# design.net
KiCad netlist of a schematic drawn in Altium Designer
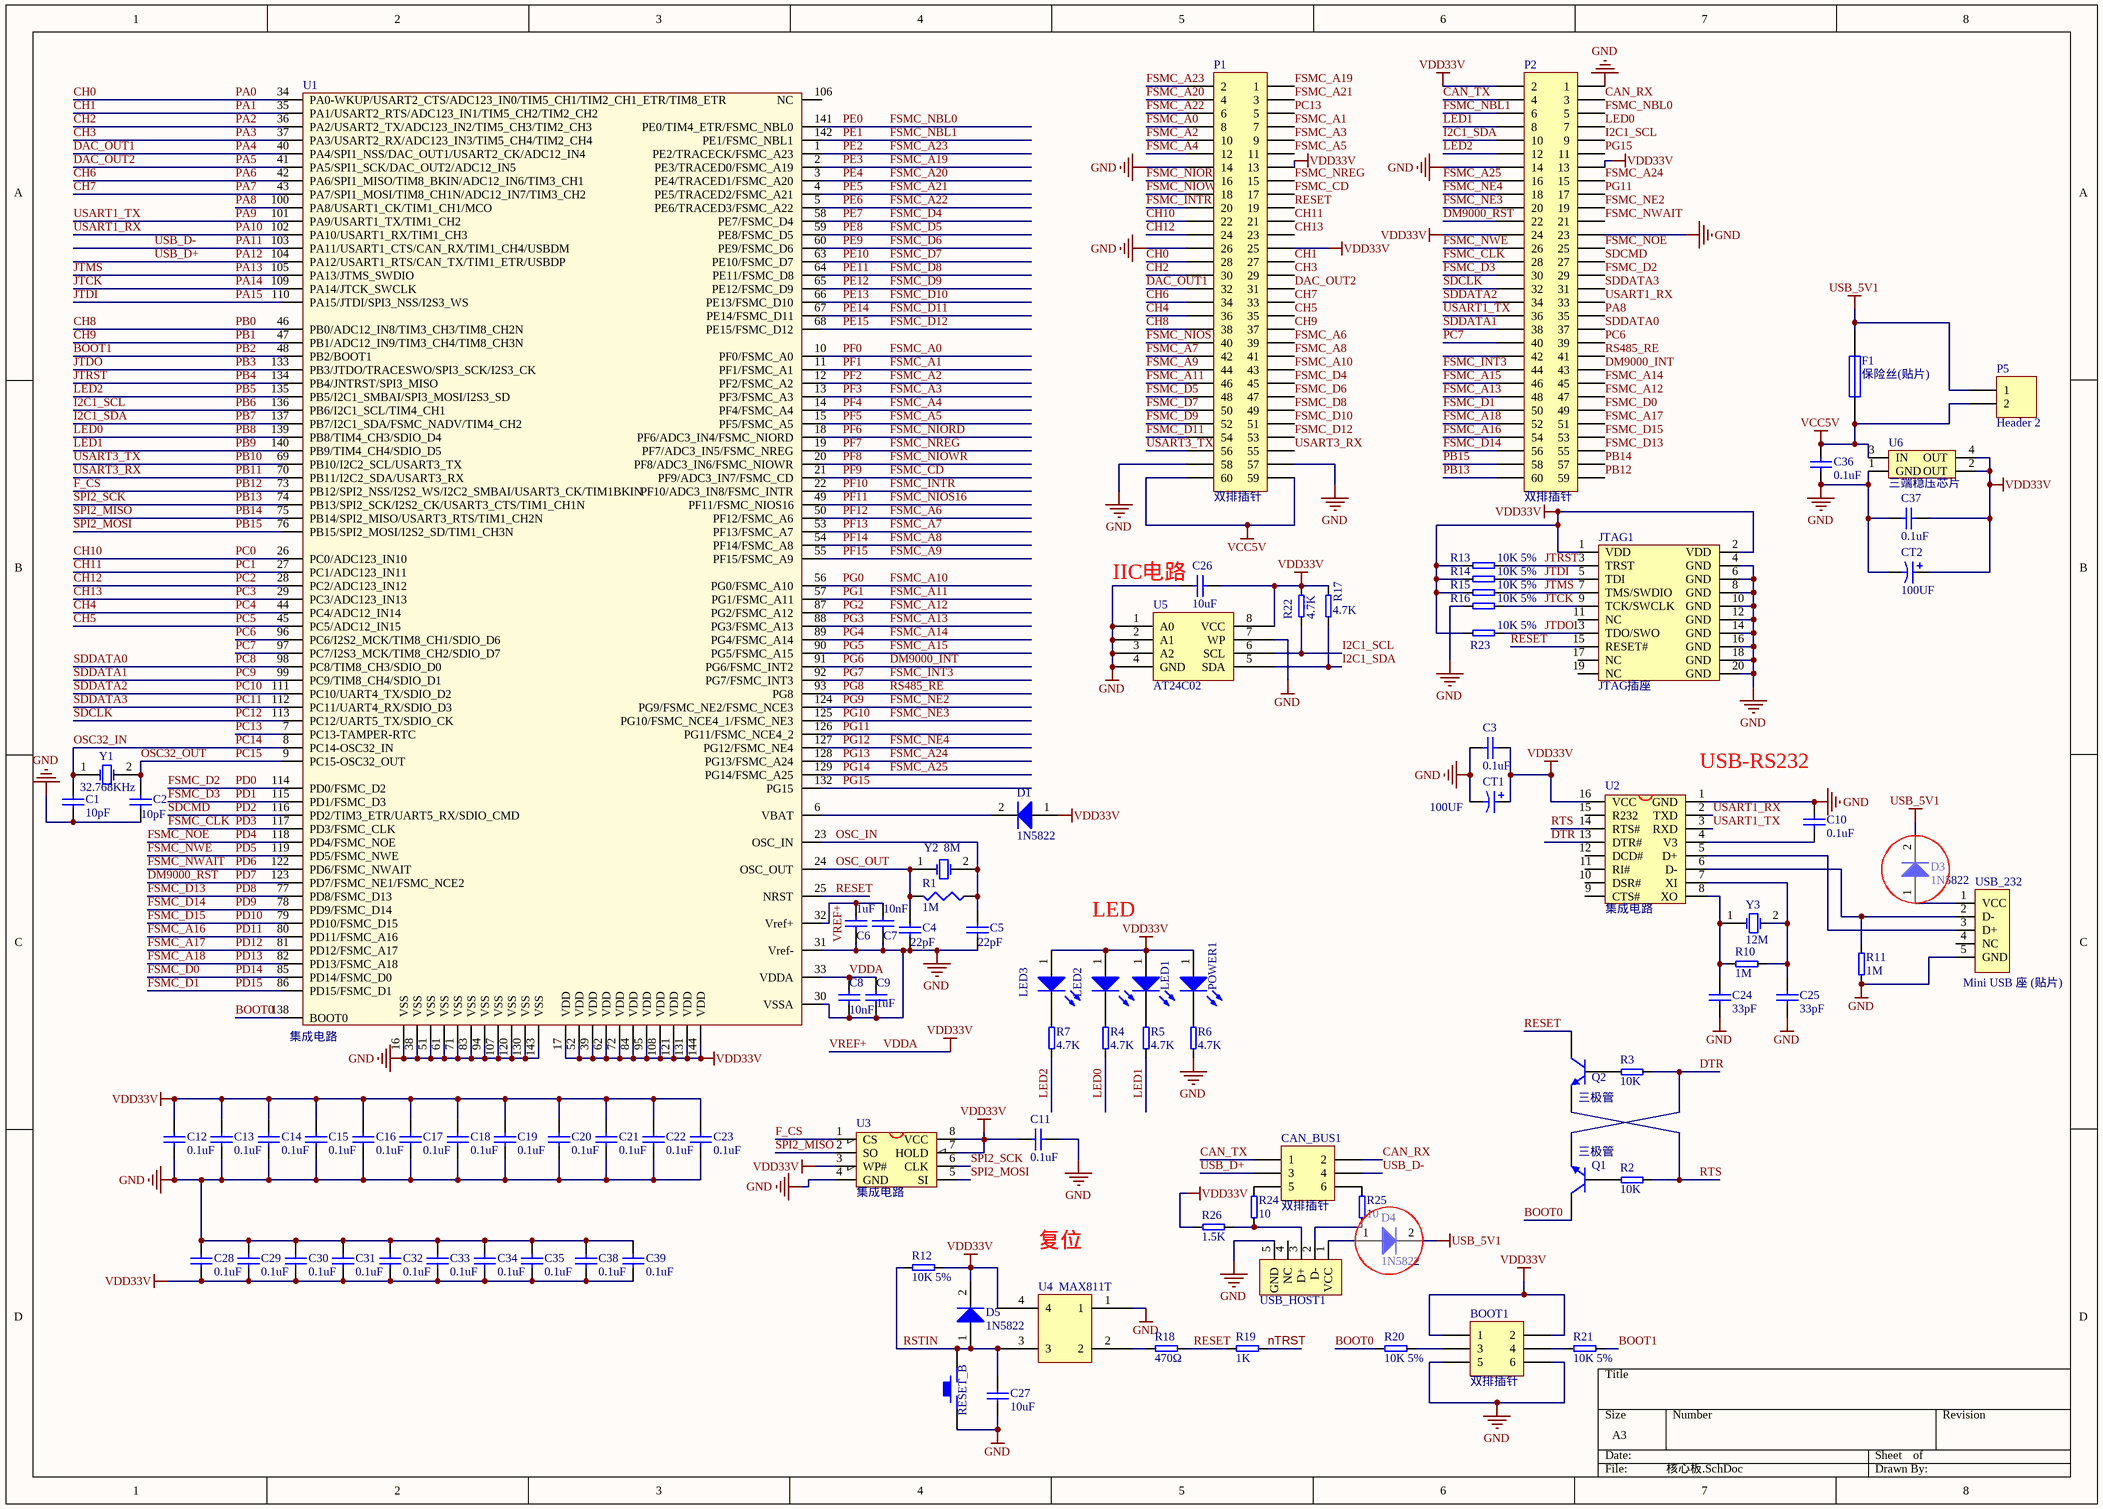
[diagram p0: 核心板.SchDoc]

(export (version "E")
  (design (tool "Eeschema 10.0.6"))
  (components
    (comp (ref "BOOT1")
      (value "双排插针")
      (footprint "HDR2X3")
      (description "2x3 脚间距2.54")
      (fields (field (name "PUBLISHER") "Altium Limited"))
      (libsource (lib "Miscellaneous Connectors") (part "Header 3X2"))
    )
    (comp (ref "C1")
      (value "10pF")
      (footprint "0603")
      (description "CAP 10PF 50V CERAMIC 0603 SMD")
      (fields (field (name "Comment") "电容(贴片)") (field (name "PUBLISHER") "Altium Limited"))
      (libsource (lib "Miscellaneous Devices") (part "Cap"))
    )
    (comp (ref "C2")
      (value "10pF")
      (footprint "0603")
      (description "CAP 10PF 50V CERAMIC 0603 SMD")
      (fields (field (name "Comment") "电容(贴片)") (field (name "PUBLISHER") "Altium Limited"))
      (libsource (lib "Miscellaneous Devices") (part "Cap"))
    )
    (comp (ref "C3")
      (value "0.1uF")
      (footprint "0603")
      (description "0603X7R104J160NT(0.1uF)")
      (fields (field (name "Comment") "电容(贴片)"))
      (libsource (lib "altium-import") (part "root_2_mirrored_CAP_0.1uF X7R 0603_"))
    )
    (comp (ref "C4")
      (value "22pF")
      (footprint "0603")
      (description "CAP 22PF 50V CERAMIC 0603 SMD")
      (fields (field (name "Comment") "电容(贴片)") (field (name "PUBLISHER") "Altium Limited"))
      (libsource (lib "Miscellaneous Devices") (part "Cap"))
    )
    (comp (ref "C5")
      (value "22pF")
      (footprint "0603")
      (description "CAP 22PF 50V CERAMIC 0603 SMD")
      (fields (field (name "Comment") "电容(贴片)") (field (name "PUBLISHER") "Altium Limited"))
      (libsource (lib "Miscellaneous Devices") (part "Cap"))
    )
    (comp (ref "C6")
      (value "1uF")
      (footprint "0603")
      (description "CAP 1uf 16V CERAMIC X5R 0603")
      (fields (field (name "Comment") "电容(贴片)") (field (name "PUBLISHER") "Altium Limited"))
      (libsource (lib "Miscellaneous Devices") (part "Cap"))
    )
    (comp (ref "C7")
      (value "10nF")
      (footprint "0603")
      (description "CAP 10nf 16V CERAMIC X5R 0603")
      (fields (field (name "Comment") "电容(贴片)") (field (name "PUBLISHER") "Altium Limited"))
      (libsource (lib "Miscellaneous Devices") (part "Cap"))
    )
    (comp (ref "C8")
      (value "10nF")
      (footprint "0603")
      (description "CAP 10nf 16V CERAMIC X5R 0603")
      (fields (field (name "Comment") "电容(贴片)") (field (name "PUBLISHER") "Altium Limited"))
      (libsource (lib "Miscellaneous Devices") (part "Cap"))
    )
    (comp (ref "C9")
      (value "1uF")
      (footprint "0603")
      (description "CAP 1uf 16V CERAMIC X5R 0603")
      (fields (field (name "Comment") "电容(贴片)") (field (name "PUBLISHER") "Altium Limited"))
      (libsource (lib "Miscellaneous Devices") (part "Cap"))
    )
    (comp (ref "C10")
      (value "0.1uF")
      (footprint "0603")
      (description "0603X7R104J160NT(0.1uF)")
      (fields (field (name "Comment") "电容(贴片)"))
      (libsource (lib "altium-import") (part "root_3_mirrored_CAP_0.1uF X7R 0603_"))
    )
    (comp (ref "C11")
      (value "0.1uF")
      (footprint "0603")
      (description "0603X7R104J160NT(0.1uF)")
      (fields (field (name "Comment") "电容(贴片)"))
      (libsource (lib "altium-import") (part "root_2_mirrored_CAP_0.1uF X7R 0603_"))
    )
    (comp (ref "C12")
      (value "0.1uF")
      (footprint "0603")
      (description "0603X7R104J160NT(0.1uF)")
      (fields (field (name "Comment") "电容(贴片)"))
      (libsource (lib "altium-import") (part "root_3_mirrored_CAP_0.1uF X7R 0603_"))
    )
    (comp (ref "C13")
      (value "0.1uF")
      (footprint "0603")
      (description "0603X7R104J160NT(0.1uF)")
      (fields (field (name "Comment") "电容(贴片)"))
      (libsource (lib "altium-import") (part "root_3_mirrored_CAP_0.1uF X7R 0603_"))
    )
    (comp (ref "C14")
      (value "0.1uF")
      (footprint "0603")
      (description "0603X7R104J160NT(0.1uF)")
      (fields (field (name "Comment") "电容(贴片)"))
      (libsource (lib "altium-import") (part "root_3_mirrored_CAP_0.1uF X7R 0603_"))
    )
    (comp (ref "C15")
      (value "0.1uF")
      (footprint "0603")
      (description "0603X7R104J160NT(0.1uF)")
      (fields (field (name "Comment") "电容(贴片)"))
      (libsource (lib "altium-import") (part "root_3_mirrored_CAP_0.1uF X7R 0603_"))
    )
    (comp (ref "C16")
      (value "0.1uF")
      (footprint "0603")
      (description "0603X7R104J160NT(0.1uF)")
      (fields (field (name "Comment") "电容(贴片)"))
      (libsource (lib "altium-import") (part "root_3_mirrored_CAP_0.1uF X7R 0603_"))
    )
    (comp (ref "C17")
      (value "0.1uF")
      (footprint "0603")
      (description "0603X7R104J160NT(0.1uF)")
      (fields (field (name "Comment") "电容(贴片)"))
      (libsource (lib "altium-import") (part "root_3_mirrored_CAP_0.1uF X7R 0603_"))
    )
    (comp (ref "C18")
      (value "0.1uF")
      (footprint "0603")
      (description "0603X7R104J160NT(0.1uF)")
      (fields (field (name "Comment") "电容(贴片)"))
      (libsource (lib "altium-import") (part "root_3_mirrored_CAP_0.1uF X7R 0603_"))
    )
    (comp (ref "C19")
      (value "0.1uF")
      (footprint "0603")
      (description "0603X7R104J160NT(0.1uF)")
      (fields (field (name "Comment") "电容(贴片)"))
      (libsource (lib "altium-import") (part "root_3_mirrored_CAP_0.1uF X7R 0603_"))
    )
    (comp (ref "C20")
      (value "0.1uF")
      (footprint "0603")
      (description "0603X7R104J160NT(0.1uF)")
      (fields (field (name "Comment") "电容(贴片)"))
      (libsource (lib "altium-import") (part "root_3_mirrored_CAP_0.1uF X7R 0603_"))
    )
    (comp (ref "C21")
      (value "0.1uF")
      (footprint "0603")
      (description "0603X7R104J160NT(0.1uF)")
      (fields (field (name "Comment") "电容(贴片)"))
      (libsource (lib "altium-import") (part "root_3_mirrored_CAP_0.1uF X7R 0603_"))
    )
    (comp (ref "C22")
      (value "0.1uF")
      (footprint "0603")
      (description "0603X7R104J160NT(0.1uF)")
      (fields (field (name "Comment") "电容(贴片)"))
      (libsource (lib "altium-import") (part "root_3_mirrored_CAP_0.1uF X7R 0603_"))
    )
    (comp (ref "C23")
      (value "0.1uF")
      (footprint "0603")
      (description "0603X7R104J160NT(0.1uF)")
      (fields (field (name "Comment") "电容(贴片)"))
      (libsource (lib "altium-import") (part "root_3_mirrored_CAP_0.1uF X7R 0603_"))
    )
    (comp (ref "C24")
      (value "33pF")
      (footprint "0603")
      (description "0603COG330J500NT(33pF)")
      (fields (field (name "Comment") "电容(贴片)"))
      (libsource (lib "altium-import") (part "root_1_mirrored_CAP_33pF COG 0603_"))
    )
    (comp (ref "C25")
      (value "33pF")
      (footprint "0603")
      (description "0603COG330J500NT(33pF)")
      (fields (field (name "Comment") "电容(贴片)"))
      (libsource (lib "altium-import") (part "root_1_mirrored_CAP_33pF COG 0603_"))
    )
    (comp (ref "C26")
      (value "10uF")
      (footprint "0603")
      (description "0603Z5U106J100NT(10uF/10V)")
      (fields (field (name "Comment") "电容(贴片)"))
      (libsource (lib "altium-import") (part "root_0_CAP_10uF/10V Z5U 0603_"))
    )
    (comp (ref "C27")
      (value "10uF")
      (footprint "0603")
      (description "0603Z5U106J100NT(10uF/10V)")
      (fields (field (name "Comment") "电容(贴片)"))
      (libsource (lib "altium-import") (part "root_3_CAP_10uF/10V Z5U 0603_"))
    )
    (comp (ref "C28")
      (value "0.1uF")
      (footprint "0603")
      (description "0603X7R104J160NT(0.1uF)")
      (fields (field (name "Comment") "电容(贴片)"))
      (libsource (lib "altium-import") (part "root_3_mirrored_CAP_0.1uF X7R 0603_"))
    )
    (comp (ref "C29")
      (value "0.1uF")
      (footprint "0603")
      (description "0603X7R104J160NT(0.1uF)")
      (fields (field (name "Comment") "电容(贴片)"))
      (libsource (lib "altium-import") (part "root_3_mirrored_CAP_0.1uF X7R 0603_"))
    )
    (comp (ref "C30")
      (value "0.1uF")
      (footprint "0603")
      (description "0603X7R104J160NT(0.1uF)")
      (fields (field (name "Comment") "电容(贴片)"))
      (libsource (lib "altium-import") (part "root_3_mirrored_CAP_0.1uF X7R 0603_"))
    )
    (comp (ref "C31")
      (value "0.1uF")
      (footprint "0603")
      (description "0603X7R104J160NT(0.1uF)")
      (fields (field (name "Comment") "电容(贴片)"))
      (libsource (lib "altium-import") (part "root_3_mirrored_CAP_0.1uF X7R 0603_"))
    )
    (comp (ref "C32")
      (value "0.1uF")
      (footprint "0603")
      (description "0603X7R104J160NT(0.1uF)")
      (fields (field (name "Comment") "电容(贴片)"))
      (libsource (lib "altium-import") (part "root_3_mirrored_CAP_0.1uF X7R 0603_"))
    )
    (comp (ref "C33")
      (value "0.1uF")
      (footprint "0603")
      (description "0603X7R104J160NT(0.1uF)")
      (fields (field (name "Comment") "电容(贴片)"))
      (libsource (lib "altium-import") (part "root_3_mirrored_CAP_0.1uF X7R 0603_"))
    )
    (comp (ref "C34")
      (value "0.1uF")
      (footprint "0603")
      (description "0603X7R104J160NT(0.1uF)")
      (fields (field (name "Comment") "电容(贴片)"))
      (libsource (lib "altium-import") (part "root_3_mirrored_CAP_0.1uF X7R 0603_"))
    )
    (comp (ref "C35")
      (value "0.1uF")
      (footprint "0603")
      (description "0603X7R104J160NT(0.1uF)")
      (fields (field (name "Comment") "电容(贴片)"))
      (libsource (lib "altium-import") (part "root_3_mirrored_CAP_0.1uF X7R 0603_"))
    )
    (comp (ref "C36")
      (value "0.1uF")
      (footprint "0603")
      (description "0603X7R104J160NT(0.1uF)")
      (fields (field (name "Comment") "电容(贴片)"))
      (libsource (lib "altium-import") (part "root_3_mirrored_CAP_0.1uF X7R 0603_"))
    )
    (comp (ref "C37")
      (value "0.1uF")
      (footprint "0603")
      (description "0603X7R104J160NT(0.1uF)")
      (fields (field (name "Comment") "电容(贴片)"))
      (libsource (lib "altium-import") (part "root_0_mirrored_CAP_0.1uF X7R 0603_"))
    )
    (comp (ref "C38")
      (value "0.1uF")
      (footprint "0603")
      (description "0603X7R104J160NT(0.1uF)")
      (fields (field (name "Comment") "电容(贴片)"))
      (libsource (lib "altium-import") (part "root_3_mirrored_CAP_0.1uF X7R 0603_"))
    )
    (comp (ref "C39")
      (value "0.1uF")
      (footprint "0603")
      (description "0603X7R104J160NT(0.1uF)")
      (fields (field (name "Comment") "电容(贴片)"))
      (libsource (lib "altium-import") (part "root_3_mirrored_CAP_0.1uF X7R 0603_"))
    )
    (comp (ref "CAN_BUS1")
      (value "双排插针")
      (footprint "HDR2X3")
      (description "2x3 Pin 脚间距2.54mm")
      (fields (field (name "PUBLISHER") "Altium Limited"))
      (libsource (lib "Miscellaneous Connectors") (part "Header 3X2"))
    )
    (comp (ref "CT1")
      (value "100UF")
      (footprint "6032")
      (description "CAP TANTALUM 100UF 16V 20% SMD")
      (fields (field (name "Comment") "钽电容(贴片)"))
      (libsource (lib "altium-import") (part "root_1_mirrored_CAP TAN 100uF/10V/6032_"))
    )
    (comp (ref "CT2")
      (value "100UF")
      (footprint "6032")
      (description "CAP TANTALUM 100UF 16V 20% SMD")
      (fields (field (name "Comment") "钽电容(贴片)"))
      (libsource (lib "altium-import") (part "root_1_mirrored_CAP TAN 100uF/10V/6032_"))
    )
    (comp (ref "D1")
      (value "1N5822")
      (footprint "D1206")
      (description "1N5822/1206")
      (fields (field (name "Comment") "二极管(贴片)"))
      (libsource (lib "altium-import") (part "root_0_mirrored_DIODE 1N4148/1206_"))
    )
    (comp (ref "D3")
      (value "1N5822")
      (footprint "D1206")
      (description "1N5822/1206")
      (fields (field (name "Comment") "二极管(贴片)"))
      (libsource (lib "altium-import") (part "root_3_mirrored_DIODE 1N4148/1206_"))
    )
    (comp (ref "D4")
      (value "1N5822")
      (footprint "D1206")
      (description "1N5822/1206")
      (fields (field (name "Comment") "二极管(贴片)"))
      (libsource (lib "altium-import") (part "root_2_mirrored_DIODE 1N4148/1206_"))
    )
    (comp (ref "D5")
      (value "1N5822")
      (footprint "D1206")
      (description "1N5822/1206")
      (fields (field (name "Comment") "二极管(贴片)"))
      (libsource (lib "altium-import") (part "root_1_DIODE 1N4148/1206_"))
    )
    (comp (ref "F1")
      (value "保险丝(贴片)")
      (footprint "0805")
      (description "0.5A 0805")
      (fields (field (name "PUBLISHER") "Altium Limited"))
      (libsource (lib "Miscellaneous Devices") (part "Fuse 1"))
    )
    (comp (ref "JTAG1")
      (value "JTAG插座")
      (footprint "JTAG_20")
      (description "20P 黑色 带缺口")
      (libsource (lib "WarShip V3 STM32103封装库") (part "JTAG"))
    )
    (comp (ref "LED1")
      (value "二极管(贴片发光绿色)")
      (footprint "LED-0805")
      (description "17-215SYGC-S530-E2-TR8")
      (libsource (lib "SCH_XIJUN") (part "LED_GREEN 0805"))
    )
    (comp (ref "LED2")
      (value "二极管(贴片发光绿色)")
      (footprint "LED-0805")
      (description "17-215SYGC-S530-E2-TR8")
      (libsource (lib "SCH_XIJUN") (part "LED_GREEN 0805"))
    )
    (comp (ref "LED3")
      (value "二极管(贴片发光绿色)")
      (footprint "LED-0805")
      (description "17-215SYGC-S530-E2-TR8")
      (libsource (lib "SCH_XIJUN") (part "LED_GREEN 0805"))
    )
    (comp (ref "P1")
      (value "双排插针")
      (footprint "HDR2X30")
      (description "双排 30*2P 脚间距 2.54mm")
      (fields (field (name "PUBLISHER") "Altium Limited"))
      (libsource (lib "Miscellaneous Connectors") (part "Header 30X2"))
    )
    (comp (ref "P2")
      (value "双排插针")
      (footprint "HDR2X30")
      (description "双排 30*2P 脚间距 2.54mm")
      (fields (field (name "PUBLISHER") "Altium Limited"))
      (libsource (lib "Miscellaneous Connectors") (part "Header 30X2"))
    )
    (comp (ref "P5")
      (value "Header 2")
      (footprint "HDR1X2")
      (description "Header, 2-Pin")
      (fields (field (name "PUBLISHER") "Altium Limited"))
      (libsource (lib "Miscellaneous Connectors") (part "Header 2"))
    )
    (comp (ref "POWER1")
      (value "二极管(贴片发光红色)")
      (footprint "LED-0805")
      (description "17-215-SURC-S530-A3-TR8")
      (libsource (lib "SCH_XIJUN") (part "LED_GREEN 0805"))
    )
    (comp (ref "Q1")
      (value "三极管")
      (footprint "sot-23")
      (description "S8050 NPN General Purpose Amplifier")
      (fields (field (name "PUBLISHER") "Altium Limited"))
      (libsource (lib "Miscellaneous Devices") (part "2N3904"))
    )
    (comp (ref "Q2")
      (value "三极管")
      (footprint "sot-23")
      (description "S8050 NPN General Purpose Amplifier")
      (fields (field (name "PUBLISHER") "Altium Limited"))
      (libsource (lib "Miscellaneous Devices") (part "2N3904"))
    )
    (comp (ref "R1")
      (value "1M")
      (footprint "0603")
      (description "RS-03K-105±5%(1MΩ)")
      (fields (field (name "Comment") "电阻(贴片)") (field (name "PUBLISHER") "Altium Limited"))
      (libsource (lib "Miscellaneous Devices") (part "Res3"))
    )
    (comp (ref "R2")
      (value "10K")
      (footprint "0603")
      (description "RS-03K-105±5%(1MΩ)")
      (fields (field (name "Comment") "电阻(贴片)"))
      (libsource (lib "altium-import") (part "root_2_mirrored_RES_1MΩ 5% 0603_"))
    )
    (comp (ref "R3")
      (value "10K")
      (footprint "0603")
      (description "RS-03K-102±5%(1K)")
      (fields (field (name "Comment") "电阻(贴片)"))
      (libsource (lib "altium-import") (part "root_0_mirrored_RES_1MΩ 5% 0603_"))
    )
    (comp (ref "R4")
      (value "4.7K")
      (footprint "0603")
      (description "RS-03K-472±5%(4.7K)")
      (fields (field (name "Comment") "电阻(贴片)"))
      (libsource (lib "SCH_XIJUN") (part "RES_4.7K  5% 0603"))
    )
    (comp (ref "R5")
      (value "4.7K")
      (footprint "0603")
      (description "RS-03K-472±5%(4.7K)")
      (fields (field (name "Comment") "电阻(贴片)"))
      (libsource (lib "SCH_XIJUN") (part "RES_4.7K  5% 0603"))
    )
    (comp (ref "R6")
      (value "4.7K")
      (footprint "0603")
      (description "RS-03K-472±5%(4.7K)")
      (fields (field (name "Comment") "电阻(贴片)"))
      (libsource (lib "SCH_XIJUN") (part "RES_4.7K  5% 0603"))
    )
    (comp (ref "R7")
      (value "4.7K")
      (footprint "0603")
      (description "RS-03K-472±5%(4.7K)")
      (fields (field (name "Comment") "电阻(贴片)"))
      (libsource (lib "SCH_XIJUN") (part "RES_4.7K  5% 0603"))
    )
    (comp (ref "R10")
      (value "1M")
      (footprint "0603")
      (description "RS-03K-105±5%(1MΩ)")
      (fields (field (name "Comment") "电阻(贴片)"))
      (libsource (lib "altium-import") (part "root_0_mirrored_RES_1MΩ 5% 0603_"))
    )
    (comp (ref "R11")
      (value "1M")
      (footprint "0603")
      (description "RS-03K-105±5%(1MΩ)")
      (fields (field (name "Comment") "电阻(贴片)"))
      (libsource (lib "altium-import") (part "root_3_mirrored_RES_1M 5% 0603_"))
    )
    (comp (ref "R12")
      (value "10K 5%")
      (footprint "0603")
      (description "RS-03K-103±5%(10KΩ)")
      (fields (field (name "Comment") "电阻(贴片)"))
      (libsource (lib "altium-import") (part "root_2_RES_10K 5% 0603_"))
    )
    (comp (ref "R13")
      (value "10K 5%")
      (footprint "0603")
      (description "RS-03K-103±5%(10KΩ)")
      (fields (field (name "Comment") "电阻(贴片)"))
      (libsource (lib "altium-import") (part "root_0_RES_10K 5% 0603_"))
    )
    (comp (ref "R14")
      (value "10K 5%")
      (footprint "0603")
      (description "RS-03K-103±5%(10KΩ)")
      (fields (field (name "Comment") "电阻(贴片)"))
      (libsource (lib "altium-import") (part "root_0_RES_10K 5% 0603_"))
    )
    (comp (ref "R15")
      (value "10K 5%")
      (footprint "0603")
      (description "RS-03K-103±5%(10KΩ)")
      (fields (field (name "Comment") "电阻(贴片)"))
      (libsource (lib "altium-import") (part "root_0_RES_10K 5% 0603_"))
    )
    (comp (ref "R16")
      (value "10K 5%")
      (footprint "0603")
      (description "RS-03K-103±5%(10KΩ)")
      (fields (field (name "Comment") "电阻(贴片)"))
      (libsource (lib "altium-import") (part "root_0_RES_10K 5% 0603_"))
    )
    (comp (ref "R17")
      (value "4.7K")
      (footprint "0603")
      (description "RS-03K-152±5%(1.5KΩ)")
      (fields (field (name "Comment") "电阻(贴片)"))
      (libsource (lib "altium-import") (part "root_1_RES_1.5K  5% 0603_"))
    )
    (comp (ref "R18")
      (value "470Ω")
      (footprint "0603")
      (description "RS-03K-471±5%(470Ω)")
      (fields (field (name "Comment") "电阻(贴片)"))
      (libsource (lib "altium-import") (part "root_2_RES_470 5% 0603_"))
    )
    (comp (ref "R19")
      (value "1K")
      (footprint "0603")
      (description "RS-03K-102±5%(1K)")
      (fields (field (name "Comment") "电阻(贴片)"))
      (libsource (lib "altium-import") (part "root_0_RES_1K  5% 0603_"))
    )
    (comp (ref "R20")
      (value "10K 5%")
      (footprint "0603")
      (description "RS-03K-103±5%(10KΩ)")
      (fields (field (name "Comment") "电阻(贴片)"))
      (libsource (lib "altium-import") (part "root_2_RES_10K 5% 0603_"))
    )
    (comp (ref "R21")
      (value "10K 5%")
      (footprint "0603")
      (description "RS-03K-103±5%(10KΩ)")
      (fields (field (name "Comment") "电阻(贴片)"))
      (libsource (lib "altium-import") (part "root_2_RES_10K 5% 0603_"))
    )
    (comp (ref "R22")
      (value "4.7K")
      (footprint "0603")
      (description "RS-03K-152±5%(1.5KΩ)")
      (fields (field (name "Comment") "电阻(贴片)"))
      (libsource (lib "altium-import") (part "root_1_RES_1.5K  5% 0603_"))
    )
    (comp (ref "R23")
      (value "10K 5%")
      (footprint "0603")
      (description "RS-03K-103±5%(10KΩ)")
      (fields (field (name "Comment") "电阻(贴片)"))
      (libsource (lib "altium-import") (part "root_0_RES_10K 5% 0603_"))
    )
    (comp (ref "R24")
      (value "10")
      (footprint "0603")
      (description "RS-03K-100±5%(10)")
      (fields (field (name "Comment") "电阻(贴片)"))
      (libsource (lib "SCH_XIJUN") (part "RES_1K  5% 0603"))
    )
    (comp (ref "R25")
      (value "10")
      (footprint "0603")
      (description "RS-03K-100±5%(10)")
      (fields (field (name "Comment") "电阻(贴片)"))
      (libsource (lib "SCH_XIJUN") (part "RES_1K  5% 0603"))
    )
    (comp (ref "R26")
      (value "1.5K")
      (footprint "0603")
      (description "RS-03K-152±5%(1.5K)")
      (fields (field (name "Comment") "电阻(贴片)"))
      (libsource (lib "SCH_XIJUN") (part "RES_1.5K  5% 0603"))
    )
    (comp (ref "RESET_B")
      (value "复位按键")
      (footprint "KEY_M")
      (description "6*6*5 黑色 直插")
      (libsource (lib "WarShip V3 STM32103封装库") (part "KEY_M"))
    )
    (comp (ref "U1")
      (value "集成电路")
      (footprint "LQFP144")
      (description "STM32F103ZET6")
      (libsource (lib "WarShip V3 STM32103封装库") (part "STM32F103ZET6"))
    )
    (comp (ref "U2")
      (value "集成电路")
      (footprint "SOP16M")
      (description "CH340G")
      (libsource (lib "WarShip V3 STM32103封装库") (part "CH340G"))
    )
    (comp (ref "U3")
      (value "集成电路")
      (footprint "SOIC-8")
      (description "W25Q128")
      (libsource (lib "WarShip V3 STM32103封装库") (part "W25X16"))
    )
    (comp (ref "U4")
      (value "MAX811T")
      (footprint "MAX811T")
      (description "MAX811T/SOT143  电源管理芯片")
      (fields (field (name "Comment") "集成电路贴片"))
      (libsource (lib "altium-import") (part "root_0_Power MAX811T_"))
    )
    (comp (ref "U5")
      (value "AT24C02")
      (footprint "SOP8")
      (description "AT24C02/SOP08")
      (fields (field (name "Comment") "集成电路贴片"))
      (libsource (lib "altium-import") (part "root_0_AT24C02A_"))
    )
    (comp (ref "U6")
      (value "三端稳压芯片")
      (footprint "AMS1117")
      (description "AMS1117-3.3")
      (libsource (lib "WarShip V3 STM32103封装库") (part "AMS1117"))
    )
    (comp (ref "USB_232")
      (value "Mini USB 座 (贴片)")
      (footprint "USB/SM0.8-6H5")
      (description "Mini USB")
      (libsource (lib "") (part "USB5_1"))
    )
    (comp (ref "USB_HOST1")
      (value "Mini USB 座 (贴片)")
      (footprint "USB/SM0.8-6H5")
      (description "Mini USB")
      (libsource (lib "WarShip V3 STM32103封装库") (part "USB5"))
    )
    (comp (ref "Y1")
      (value "32.768KHz")
      (footprint "32.768khz")
      (description "HC-49DIP/32.768KHz")
      (fields (field (name "Comment") "晶体(直插)") (field (name "PUBLISHER") "Altium Limited"))
      (libsource (lib "altium-import") (part "root_0_CRYSTAL 12M HC-49SMD_"))
    )
    (comp (ref "Y2")
      (value "8M")
      (footprint "CRYSTAL_SMD")
      (description "HC-49SMD/8.000MHz")
      (fields (field (name "Comment") "晶体(贴片)") (field (name "PUBLISHER") "Altium Limited"))
      (libsource (lib "altium-import") (part "root_0_CRYSTAL 12M HC-49SMD_"))
    )
    (comp (ref "Y3")
      (value "12M")
      (footprint "CRYSTAL_SMD")
      (description "HC-49SMD/12.000MHz")
      (fields (field (name "Comment") "晶体(贴片)") (field (name "PUBLISHER") "Altium Limited"))
      (libsource (lib "altium-import") (part "root_2_mirrored_CRYSTAL 12M HC-49SMD_"))
    )
  )
  (nets
    (net (code "1") (name "/BOOT0") (class "Default")
      (node (ref "Q1") (pin "3") (pinfunction "C_3") (pintype "passive"))
      (node (ref "R20") (pin "2") (pinfunction "2_2") (pintype "passive"))
      (node (ref "U1") (pin "138") (pinfunction "BOOT0_138") (pintype "passive"))
    )
    (net (code "2") (name "/BOOT1") (class "Default")
      (node (ref "R21") (pin "1") (pinfunction "1_1") (pintype "passive"))
      (node (ref "U1") (pin "48") (pinfunction "PB2/BOOT1_48") (pintype "passive"))
    )
    (net (code "3") (name "/CAN_RX") (class "Default")
      (node (ref "CAN_BUS1") (pin "2") (pinfunction "2_2") (pintype "passive"))
      (node (ref "P2") (pin "3") (pinfunction "3_3") (pintype "passive"))
    )
    (net (code "4") (name "/CAN_TX") (class "Default")
      (node (ref "CAN_BUS1") (pin "1") (pinfunction "1_1") (pintype "passive"))
      (node (ref "P2") (pin "4") (pinfunction "4_4") (pintype "passive"))
    )
    (net (code "5") (name "/CH0") (class "Default")
      (node (ref "P1") (pin "28") (pinfunction "28_28") (pintype "passive"))
      (node (ref "U1") (pin "34") (pinfunction "PA0-WKUP/USART2_CTS/ADC123_IN0/TIM5_CH1/TIM2_CH1_ETR/TIM8_ETR_34") (pintype "passive"))
    )
    (net (code "6") (name "/CH1") (class "Default")
      (node (ref "P1") (pin "27") (pinfunction "27_27") (pintype "passive"))
      (node (ref "U1") (pin "35") (pinfunction "PA1/USART2_RTS/ADC123_IN1/TIM5_CH2/TIM2_CH2_35") (pintype "passive"))
    )
    (net (code "7") (name "/CH2") (class "Default")
      (node (ref "P1") (pin "30") (pinfunction "30_30") (pintype "passive"))
      (node (ref "U1") (pin "36") (pinfunction "PA2/USART2_TX/ADC123_IN2/TIM5_CH3/TIM2_CH3_36") (pintype "passive"))
    )
    (net (code "8") (name "/CH3") (class "Default")
      (node (ref "P1") (pin "29") (pinfunction "29_29") (pintype "passive"))
      (node (ref "U1") (pin "37") (pinfunction "PA3/USART2_RX/ADC123_IN3/TIM5_CH4/TIM2_CH4_37") (pintype "passive"))
    )
    (net (code "9") (name "/CH4") (class "Default")
      (node (ref "P1") (pin "36") (pinfunction "36_36") (pintype "passive"))
      (node (ref "U1") (pin "44") (pinfunction "PC4/ADC12_IN14_44") (pintype "passive"))
    )
    (net (code "10") (name "/CH5") (class "Default")
      (node (ref "P1") (pin "35") (pinfunction "35_35") (pintype "passive"))
      (node (ref "U1") (pin "45") (pinfunction "PC5/ADC12_IN15_45") (pintype "passive"))
    )
    (net (code "11") (name "/CH6") (class "Default")
      (node (ref "P1") (pin "34") (pinfunction "34_34") (pintype "passive"))
      (node (ref "U1") (pin "42") (pinfunction "PA6/SPI1_MISO/TIM8_BKIN/ADC12_IN6/TIM3_CH1_42") (pintype "passive"))
    )
    (net (code "12") (name "/CH7") (class "Default")
      (node (ref "P1") (pin "33") (pinfunction "33_33") (pintype "passive"))
      (node (ref "U1") (pin "43") (pinfunction "PA7/SPI1_MOSI/TIM8_CH1N/ADC12_IN7/TIM3_CH2_43") (pintype "passive"))
    )
    (net (code "13") (name "/CH8") (class "Default")
      (node (ref "P1") (pin "38") (pinfunction "38_38") (pintype "passive"))
      (node (ref "U1") (pin "46") (pinfunction "PB0/ADC12_IN8/TIM3_CH3/TIM8_CH2N_46") (pintype "passive"))
    )
    (net (code "14") (name "/CH9") (class "Default")
      (node (ref "P1") (pin "37") (pinfunction "37_37") (pintype "passive"))
      (node (ref "U1") (pin "47") (pinfunction "PB1/ADC12_IN9/TIM3_CH4/TIM8_CH3N_47") (pintype "passive"))
    )
    (net (code "15") (name "/CH10") (class "Default")
      (node (ref "P1") (pin "22") (pinfunction "22_22") (pintype "passive"))
      (node (ref "U1") (pin "26") (pinfunction "PC0/ADC123_IN10_26") (pintype "passive"))
    )
    (net (code "16") (name "/CH11") (class "Default")
      (node (ref "P1") (pin "21") (pinfunction "21_21") (pintype "passive"))
      (node (ref "U1") (pin "27") (pinfunction "PC1/ADC123_IN11_27") (pintype "passive"))
    )
    (net (code "17") (name "/CH12") (class "Default")
      (node (ref "P1") (pin "24") (pinfunction "24_24") (pintype "passive"))
      (node (ref "U1") (pin "28") (pinfunction "PC2/ADC123_IN12_28") (pintype "passive"))
    )
    (net (code "18") (name "/CH13") (class "Default")
      (node (ref "P1") (pin "23") (pinfunction "23_23") (pintype "passive"))
      (node (ref "U1") (pin "29") (pinfunction "PC3/ADC123_IN13_29") (pintype "passive"))
    )
    (net (code "19") (name "/DAC_OUT1") (class "Default")
      (node (ref "P1") (pin "32") (pinfunction "32_32") (pintype "passive"))
      (node (ref "U1") (pin "40") (pinfunction "PA4/SPI1_NSS/DAC_OUT1/USART2_CK/ADC12_IN4_40") (pintype "passive"))
    )
    (net (code "20") (name "/DAC_OUT2") (class "Default")
      (node (ref "P1") (pin "31") (pinfunction "31_31") (pintype "passive"))
      (node (ref "U1") (pin "41") (pinfunction "PA5/SPI1_SCK/DAC_OUT2/ADC12_IN5_41") (pintype "passive"))
    )
    (net (code "21") (name "/DM9000_INT") (class "Default")
      (node (ref "P2") (pin "43") (pinfunction "43_43") (pintype "passive"))
      (node (ref "U1") (pin "91") (pinfunction "PG6/FSMC_INT2_91") (pintype "passive"))
    )
    (net (code "22") (name "/DM9000_RST") (class "Default")
      (node (ref "P2") (pin "22") (pinfunction "22_22") (pintype "passive"))
      (node (ref "U1") (pin "123") (pinfunction "PD7/FSMC_NE1/FSMC_NCE2_123") (pintype "passive"))
    )
    (net (code "23") (name "/DTR") (class "Default")
      (node (ref "Q1") (pin "1") (pinfunction "E_1") (pintype "passive"))
      (node (ref "R3") (pin "1") (pinfunction "1_1") (pintype "passive"))
      (node (ref "U2") (pin "13") (pinfunction "DTR#_13") (pintype "passive"))
    )
    (net (code "24") (name "/FSMC_A0") (class "Default")
      (node (ref "P1") (pin "8") (pinfunction "8_8") (pintype "passive"))
      (node (ref "U1") (pin "10") (pinfunction "PF0/FSMC_A0_10") (pintype "passive"))
    )
    (net (code "25") (name "/FSMC_A1") (class "Default")
      (node (ref "P1") (pin "7") (pinfunction "7_7") (pintype "passive"))
      (node (ref "U1") (pin "11") (pinfunction "PF1/FSMC_A1_11") (pintype "passive"))
    )
    (net (code "26") (name "/FSMC_A2") (class "Default")
      (node (ref "P1") (pin "10") (pinfunction "10_10") (pintype "passive"))
      (node (ref "U1") (pin "12") (pinfunction "PF2/FSMC_A2_12") (pintype "passive"))
    )
    (net (code "27") (name "/FSMC_A3") (class "Default")
      (node (ref "P1") (pin "9") (pinfunction "9_9") (pintype "passive"))
      (node (ref "U1") (pin "13") (pinfunction "PF3/FSMC_A3_13") (pintype "passive"))
    )
    (net (code "28") (name "/FSMC_A4") (class "Default")
      (node (ref "P1") (pin "12") (pinfunction "12_12") (pintype "passive"))
      (node (ref "U1") (pin "14") (pinfunction "PF4/FSMC_A4_14") (pintype "passive"))
    )
    (net (code "29") (name "/FSMC_A5") (class "Default")
      (node (ref "P1") (pin "11") (pinfunction "11_11") (pintype "passive"))
      (node (ref "U1") (pin "15") (pinfunction "PF5/FSMC_A5_15") (pintype "passive"))
    )
    (net (code "30") (name "/FSMC_A6") (class "Default")
      (node (ref "P1") (pin "39") (pinfunction "39_39") (pintype "passive"))
      (node (ref "U1") (pin "50") (pinfunction "PF12/FSMC_A6_50") (pintype "passive"))
    )
    (net (code "31") (name "/FSMC_A7") (class "Default")
      (node (ref "P1") (pin "42") (pinfunction "42_42") (pintype "passive"))
      (node (ref "U1") (pin "53") (pinfunction "PF13/FSMC_A7_53") (pintype "passive"))
    )
    (net (code "32") (name "/FSMC_A8") (class "Default")
      (node (ref "P1") (pin "41") (pinfunction "41_41") (pintype "passive"))
      (node (ref "U1") (pin "54") (pinfunction "PF14/FSMC_A8_54") (pintype "passive"))
    )
    (net (code "33") (name "/FSMC_A9") (class "Default")
      (node (ref "P1") (pin "44") (pinfunction "44_44") (pintype "passive"))
      (node (ref "U1") (pin "55") (pinfunction "PF15/FSMC_A9_55") (pintype "passive"))
    )
    (net (code "34") (name "/FSMC_A10") (class "Default")
      (node (ref "P1") (pin "43") (pinfunction "43_43") (pintype "passive"))
      (node (ref "U1") (pin "56") (pinfunction "PG0/FSMC_A10_56") (pintype "passive"))
    )
    (net (code "35") (name "/FSMC_A11") (class "Default")
      (node (ref "P1") (pin "46") (pinfunction "46_46") (pintype "passive"))
      (node (ref "U1") (pin "57") (pinfunction "PG1/FSMC_A11_57") (pintype "passive"))
    )
    (net (code "36") (name "/FSMC_A12") (class "Default")
      (node (ref "P2") (pin "47") (pinfunction "47_47") (pintype "passive"))
      (node (ref "U1") (pin "87") (pinfunction "PG2/FSMC_A12_87") (pintype "passive"))
    )
    (net (code "37") (name "/FSMC_A13") (class "Default")
      (node (ref "P2") (pin "48") (pinfunction "48_48") (pintype "passive"))
      (node (ref "U1") (pin "88") (pinfunction "PG3/FSMC_A13_88") (pintype "passive"))
    )
    (net (code "38") (name "/FSMC_A14") (class "Default")
      (node (ref "P2") (pin "45") (pinfunction "45_45") (pintype "passive"))
      (node (ref "U1") (pin "89") (pinfunction "PG4/FSMC_A14_89") (pintype "passive"))
    )
    (net (code "39") (name "/FSMC_A15") (class "Default")
      (node (ref "P2") (pin "46") (pinfunction "46_46") (pintype "passive"))
      (node (ref "U1") (pin "90") (pinfunction "PG5/FSMC_A15_90") (pintype "passive"))
    )
    (net (code "40") (name "/FSMC_A16") (class "Default")
      (node (ref "P2") (pin "54") (pinfunction "54_54") (pintype "passive"))
      (node (ref "U1") (pin "80") (pinfunction "PD11/FSMC_A16_80") (pintype "passive"))
    )
    (net (code "41") (name "/FSMC_A17") (class "Default")
      (node (ref "P2") (pin "51") (pinfunction "51_51") (pintype "passive"))
      (node (ref "U1") (pin "81") (pinfunction "PD12/FSMC_A17_81") (pintype "passive"))
    )
    (net (code "42") (name "/FSMC_A18") (class "Default")
      (node (ref "P2") (pin "52") (pinfunction "52_52") (pintype "passive"))
      (node (ref "U1") (pin "82") (pinfunction "PD13/FSMC_A18_82") (pintype "passive"))
    )
    (net (code "43") (name "/FSMC_A19") (class "Default")
      (node (ref "P1") (pin "1") (pinfunction "1_1") (pintype "passive"))
      (node (ref "U1") (pin "2") (pinfunction "PE3/TRACED0/FSMC_A19_2") (pintype "passive"))
    )
    (net (code "44") (name "/FSMC_A20") (class "Default")
      (node (ref "P1") (pin "4") (pinfunction "4_4") (pintype "passive"))
      (node (ref "U1") (pin "3") (pinfunction "PE4/TRACED1/FSMC_A20_3") (pintype "passive"))
    )
    (net (code "45") (name "/FSMC_A21") (class "Default")
      (node (ref "P1") (pin "3") (pinfunction "3_3") (pintype "passive"))
      (node (ref "U1") (pin "4") (pinfunction "PE5/TRACED2/FSMC_A21_4") (pintype "passive"))
    )
    (net (code "46") (name "/FSMC_A22") (class "Default")
      (node (ref "P1") (pin "6") (pinfunction "6_6") (pintype "passive"))
      (node (ref "U1") (pin "5") (pinfunction "PE6/TRACED3/FSMC_A22_5") (pintype "passive"))
    )
    (net (code "47") (name "/FSMC_A23") (class "Default")
      (node (ref "P1") (pin "2") (pinfunction "2_2") (pintype "passive"))
      (node (ref "U1") (pin "1") (pinfunction "PE2/TRACECK/FSMC_A23_1") (pintype "passive"))
    )
    (net (code "48") (name "/FSMC_A24") (class "Default")
      (node (ref "P2") (pin "15") (pinfunction "15_15") (pintype "passive"))
      (node (ref "U1") (pin "128") (pinfunction "PG13/FSMC_A24_128") (pintype "passive"))
    )
    (net (code "49") (name "/FSMC_A25") (class "Default")
      (node (ref "P2") (pin "16") (pinfunction "16_16") (pintype "passive"))
      (node (ref "U1") (pin "129") (pinfunction "PG14/FSMC_A25_129") (pintype "passive"))
    )
    (net (code "50") (name "/FSMC_CD") (class "Default")
      (node (ref "P1") (pin "17") (pinfunction "17_17") (pintype "passive"))
      (node (ref "U1") (pin "21") (pinfunction "PF9/ADC3_IN7/FSMC_CD_21") (pintype "passive"))
    )
    (net (code "51") (name "/FSMC_CLK") (class "Default")
      (node (ref "P2") (pin "28") (pinfunction "28_28") (pintype "passive"))
      (node (ref "U1") (pin "117") (pinfunction "PD3/FSMC_CLK_117") (pintype "passive"))
    )
    (net (code "52") (name "/FSMC_D0") (class "Default")
      (node (ref "P2") (pin "49") (pinfunction "49_49") (pintype "passive"))
      (node (ref "U1") (pin "85") (pinfunction "PD14/FSMC_D0_85") (pintype "passive"))
    )
    (net (code "53") (name "/FSMC_D1") (class "Default")
      (node (ref "P2") (pin "50") (pinfunction "50_50") (pintype "passive"))
      (node (ref "U1") (pin "86") (pinfunction "PD15/FSMC_D1_86") (pintype "passive"))
    )
    (net (code "54") (name "/FSMC_D2") (class "Default")
      (node (ref "P2") (pin "29") (pinfunction "29_29") (pintype "passive"))
      (node (ref "U1") (pin "114") (pinfunction "PD0/FSMC_D2_114") (pintype "passive"))
    )
    (net (code "55") (name "/FSMC_D3") (class "Default")
      (node (ref "P2") (pin "30") (pinfunction "30_30") (pintype "passive"))
      (node (ref "U1") (pin "115") (pinfunction "PD1/FSMC_D3_115") (pintype "passive"))
    )
    (net (code "56") (name "/FSMC_D4") (class "Default")
      (node (ref "P1") (pin "45") (pinfunction "45_45") (pintype "passive"))
      (node (ref "U1") (pin "58") (pinfunction "PE7/FSMC_D4_58") (pintype "passive"))
    )
    (net (code "57") (name "/FSMC_D5") (class "Default")
      (node (ref "P1") (pin "48") (pinfunction "48_48") (pintype "passive"))
      (node (ref "U1") (pin "59") (pinfunction "PE8/FSMC_D5_59") (pintype "passive"))
    )
    (net (code "58") (name "/FSMC_D6") (class "Default")
      (node (ref "P1") (pin "47") (pinfunction "47_47") (pintype "passive"))
      (node (ref "U1") (pin "60") (pinfunction "PE9/FSMC_D6_60") (pintype "passive"))
    )
    (net (code "59") (name "/FSMC_D7") (class "Default")
      (node (ref "P1") (pin "50") (pinfunction "50_50") (pintype "passive"))
      (node (ref "U1") (pin "63") (pinfunction "PE10/FSMC_D7_63") (pintype "passive"))
    )
    (net (code "60") (name "/FSMC_D8") (class "Default")
      (node (ref "P1") (pin "49") (pinfunction "49_49") (pintype "passive"))
      (node (ref "U1") (pin "64") (pinfunction "PE11/FSMC_D8_64") (pintype "passive"))
    )
    (net (code "61") (name "/FSMC_D9") (class "Default")
      (node (ref "P1") (pin "52") (pinfunction "52_52") (pintype "passive"))
      (node (ref "U1") (pin "65") (pinfunction "PE12/FSMC_D9_65") (pintype "passive"))
    )
    (net (code "62") (name "/FSMC_D10") (class "Default")
      (node (ref "P1") (pin "51") (pinfunction "51_51") (pintype "passive"))
      (node (ref "U1") (pin "66") (pinfunction "PE13/FSMC_D10_66") (pintype "passive"))
    )
    (net (code "63") (name "/FSMC_D11") (class "Default")
      (node (ref "P1") (pin "54") (pinfunction "54_54") (pintype "passive"))
      (node (ref "U1") (pin "67") (pinfunction "PE14/FSMC_D11_67") (pintype "passive"))
    )
    (net (code "64") (name "/FSMC_D12") (class "Default")
      (node (ref "P1") (pin "53") (pinfunction "53_53") (pintype "passive"))
      (node (ref "U1") (pin "68") (pinfunction "PE15/FSMC_D12_68") (pintype "passive"))
    )
    (net (code "65") (name "/FSMC_D13") (class "Default")
      (node (ref "P2") (pin "55") (pinfunction "55_55") (pintype "passive"))
      (node (ref "U1") (pin "77") (pinfunction "PD8/FSMC_D13_77") (pintype "passive"))
    )
    (net (code "66") (name "/FSMC_D14") (class "Default")
      (node (ref "P2") (pin "56") (pinfunction "56_56") (pintype "passive"))
      (node (ref "U1") (pin "78") (pinfunction "PD9/FSMC_D14_78") (pintype "passive"))
    )
    (net (code "67") (name "/FSMC_D15") (class "Default")
      (node (ref "P2") (pin "53") (pinfunction "53_53") (pintype "passive"))
      (node (ref "U1") (pin "79") (pinfunction "PD10/FSMC_D15_79") (pintype "passive"))
    )
    (net (code "68") (name "/FSMC_INT3") (class "Default")
      (node (ref "P2") (pin "44") (pinfunction "44_44") (pintype "passive"))
      (node (ref "U1") (pin "92") (pinfunction "PG7/FSMC_INT3_92") (pintype "passive"))
    )
    (net (code "69") (name "/FSMC_INTR") (class "Default")
      (node (ref "P1") (pin "20") (pinfunction "20_20") (pintype "passive"))
      (node (ref "U1") (pin "22") (pinfunction "PF10/ADC3_IN8/FSMC_INTR_22") (pintype "passive"))
    )
    (net (code "70") (name "/FSMC_NBL0") (class "Default")
      (node (ref "P2") (pin "5") (pinfunction "5_5") (pintype "passive"))
      (node (ref "U1") (pin "141") (pinfunction "PE0/TIM4_ETR/FSMC_NBL0_141") (pintype "passive"))
    )
    (net (code "71") (name "/FSMC_NBL1") (class "Default")
      (node (ref "P2") (pin "6") (pinfunction "6_6") (pintype "passive"))
      (node (ref "U1") (pin "142") (pinfunction "PE1/FSMC_NBL1_142") (pintype "passive"))
    )
    (net (code "72") (name "/FSMC_NE2") (class "Default")
      (node (ref "P2") (pin "19") (pinfunction "19_19") (pintype "passive"))
      (node (ref "U1") (pin "124") (pinfunction "PG9/FSMC_NE2/FSMC_NCE3_124") (pintype "passive"))
    )
    (net (code "73") (name "/FSMC_NE3") (class "Default")
      (node (ref "P2") (pin "20") (pinfunction "20_20") (pintype "passive"))
      (node (ref "U1") (pin "125") (pinfunction "PG10/FSMC_NCE4_1/FSMC_NE3_125") (pintype "passive"))
    )
    (net (code "74") (name "/FSMC_NE4") (class "Default")
      (node (ref "P2") (pin "18") (pinfunction "18_18") (pintype "passive"))
      (node (ref "U1") (pin "127") (pinfunction "PG12/FSMC_NE4_127") (pintype "passive"))
    )
    (net (code "75") (name "/FSMC_NIORD") (class "Default")
      (node (ref "P1") (pin "16") (pinfunction "16_16") (pintype "passive"))
      (node (ref "U1") (pin "18") (pinfunction "PF6/ADC3_IN4/FSMC_NIORD_18") (pintype "passive"))
    )
    (net (code "76") (name "/FSMC_NIOS16") (class "Default")
      (node (ref "P1") (pin "40") (pinfunction "40_40") (pintype "passive"))
      (node (ref "U1") (pin "49") (pinfunction "PF11/FSMC_NIOS16_49") (pintype "passive"))
    )
    (net (code "77") (name "/FSMC_NIOWR") (class "Default")
      (node (ref "P1") (pin "18") (pinfunction "18_18") (pintype "passive"))
      (node (ref "U1") (pin "20") (pinfunction "PF8/ADC3_IN6/FSMC_NIOWR_20") (pintype "passive"))
    )
    (net (code "78") (name "/FSMC_NOE") (class "Default")
      (node (ref "P2") (pin "25") (pinfunction "25_25") (pintype "passive"))
      (node (ref "U1") (pin "118") (pinfunction "PD4/FSMC_NOE_118") (pintype "passive"))
    )
    (net (code "79") (name "/FSMC_NREG") (class "Default")
      (node (ref "P1") (pin "15") (pinfunction "15_15") (pintype "passive"))
      (node (ref "U1") (pin "19") (pinfunction "PF7/ADC3_IN5/FSMC_NREG_19") (pintype "passive"))
    )
    (net (code "80") (name "/FSMC_NWAIT") (class "Default")
      (node (ref "P2") (pin "21") (pinfunction "21_21") (pintype "passive"))
      (node (ref "U1") (pin "122") (pinfunction "PD6/FSMC_NWAIT_122") (pintype "passive"))
    )
    (net (code "81") (name "/FSMC_NWE") (class "Default")
      (node (ref "P2") (pin "26") (pinfunction "26_26") (pintype "passive"))
      (node (ref "U1") (pin "119") (pinfunction "PD5/FSMC_NWE_119") (pintype "passive"))
    )
    (net (code "82") (name "/F_CS") (class "Default")
      (node (ref "P2") (pin "59") (pinfunction "59_59") (pintype "passive"))
      (node (ref "U1") (pin "73") (pinfunction "PB12/SPI2_NSS/I2S2_WS/I2C2_SMBAI/USART3_CK/TIM1BKIN_73") (pintype "passive"))
      (node (ref "U3") (pin "1") (pinfunction "CS_1") (pintype "passive"))
    )
    (net (code "83") (name "/I2C1_SCL") (class "Default")
      (node (ref "P2") (pin "9") (pinfunction "9_9") (pintype "passive"))
      (node (ref "R22") (pin "1") (pinfunction "1_1") (pintype "passive"))
      (node (ref "U1") (pin "136") (pinfunction "PB6/I2C1_SCL/TIM4_CH1_136") (pintype "passive"))
      (node (ref "U5") (pin "6") (pinfunction "SCL_6") (pintype "passive"))
    )
    (net (code "84") (name "/I2C1_SDA") (class "Default")
      (node (ref "P2") (pin "10") (pinfunction "10_10") (pintype "passive"))
      (node (ref "R17") (pin "1") (pinfunction "1_1") (pintype "passive"))
      (node (ref "U1") (pin "137") (pinfunction "PB7/I2C1_SDA/FSMC_NADV/TIM4_CH2_137") (pintype "passive"))
      (node (ref "U5") (pin "5") (pinfunction "SDA_5") (pintype "passive"))
    )
    (net (code "85") (name "/JTCK") (class "Default")
      (node (ref "JTAG1") (pin "9") (pinfunction "TCK/SWCLK_9") (pintype "passive"))
      (node (ref "R16") (pin "2") (pinfunction "2_2") (pintype "passive"))
      (node (ref "U1") (pin "109") (pinfunction "PA14/JTCK_SWCLK_109") (pintype "passive"))
    )
    (net (code "86") (name "/JTDI") (class "Default")
      (node (ref "JTAG1") (pin "5") (pinfunction "TDI_5") (pintype "passive"))
      (node (ref "R14") (pin "2") (pinfunction "2_2") (pintype "passive"))
      (node (ref "U1") (pin "110") (pinfunction "PA15/JTDI/SPI3_NSS/I2S3_WS_110") (pintype "passive"))
    )
    (net (code "87") (name "/JTDO") (class "Default")
      (node (ref "JTAG1") (pin "13") (pinfunction "TDO/SWO_13") (pintype "passive"))
      (node (ref "R23") (pin "2") (pinfunction "2_2") (pintype "passive"))
      (node (ref "U1") (pin "133") (pinfunction "PB3/JTDO/TRACESWO/SPI3_SCK/I2S3_CK_133") (pintype "passive"))
    )
    (net (code "88") (name "/JTMS") (class "Default")
      (node (ref "JTAG1") (pin "7") (pinfunction "TMS/SWDIO_7") (pintype "passive"))
      (node (ref "R15") (pin "2") (pinfunction "2_2") (pintype "passive"))
      (node (ref "U1") (pin "105") (pinfunction "PA13/JTMS_SWDIO_105") (pintype "passive"))
    )
    (net (code "89") (name "/JTRST") (class "Default")
      (node (ref "JTAG1") (pin "3") (pinfunction "TRST_3") (pintype "passive"))
      (node (ref "R13") (pin "2") (pinfunction "2_2") (pintype "passive"))
      (node (ref "U1") (pin "134") (pinfunction "PB4/JNTRST/SPI3_MISO_134") (pintype "passive"))
    )
    (net (code "90") (name "/LED0") (class "Default")
      (node (ref "P2") (pin "7") (pinfunction "7_7") (pintype "passive"))
      (node (ref "R4") (pin "1") (pinfunction "1_1") (pintype "passive"))
      (node (ref "U1") (pin "139") (pinfunction "PB8/TIM4_CH3/SDIO_D4_139") (pintype "passive"))
    )
    (net (code "91") (name "/LED1") (class "Default")
      (node (ref "P2") (pin "8") (pinfunction "8_8") (pintype "passive"))
      (node (ref "R5") (pin "1") (pinfunction "1_1") (pintype "passive"))
      (node (ref "U1") (pin "140") (pinfunction "PB9/TIM4_CH4/SDIO_D5_140") (pintype "passive"))
    )
    (net (code "92") (name "/LED2") (class "Default")
      (node (ref "P2") (pin "12") (pinfunction "12_12") (pintype "passive"))
      (node (ref "R7") (pin "1") (pinfunction "1_1") (pintype "passive"))
      (node (ref "U1") (pin "135") (pinfunction "PB5/I2C1_SMBAI/SPI3_MOSI/I2S3_SD_135") (pintype "passive"))
    )
    (net (code "93") (name "/OSC32_IN") (class "Default")
      (node (ref "C1") (pin "1") (pinfunction "1_1") (pintype "passive"))
      (node (ref "U1") (pin "8") (pinfunction "PC14-OSC32_IN_8") (pintype "passive"))
      (node (ref "Y1") (pin "1") (pinfunction "OSC1_1") (pintype "passive"))
    )
    (net (code "94") (name "/OSC32_OUT") (class "Default")
      (node (ref "C2") (pin "1") (pinfunction "1_1") (pintype "passive"))
      (node (ref "U1") (pin "9") (pinfunction "PC15-OSC32_OUT_9") (pintype "passive"))
      (node (ref "Y1") (pin "2") (pinfunction "OSC2_2") (pintype "passive"))
    )
    (net (code "95") (name "/OSC_IN") (class "Default")
      (node (ref "C5") (pin "1") (pinfunction "1_1") (pintype "passive"))
      (node (ref "R1") (pin "1") (pinfunction "1_1") (pintype "passive"))
      (node (ref "U1") (pin "23") (pinfunction "OSC_IN_23") (pintype "passive"))
      (node (ref "Y2") (pin "2") (pinfunction "OSC2_2") (pintype "passive"))
    )
    (net (code "96") (name "/OSC_OUT") (class "Default")
      (node (ref "C4") (pin "1") (pinfunction "1_1") (pintype "passive"))
      (node (ref "R1") (pin "2") (pinfunction "2_2") (pintype "passive"))
      (node (ref "U1") (pin "24") (pinfunction "OSC_OUT_24") (pintype "passive"))
      (node (ref "Y2") (pin "1") (pinfunction "OSC1_1") (pintype "passive"))
    )
    (net (code "97") (name "/PA8") (class "Default")
      (node (ref "P2") (pin "35") (pinfunction "35_35") (pintype "passive"))
      (node (ref "U1") (pin "100") (pinfunction "PA8/USART1_CK/TIM1_CH1/MCO_100") (pintype "passive"))
    )
    (net (code "98") (name "/PA9") (class "Default")
      (node (ref "P2") (pin "36") (pinfunction "36_36") (pintype "passive"))
      (node (ref "U1") (pin "101") (pinfunction "PA9/USART1_TX/TIM1_CH2_101") (pintype "passive"))
      (node (ref "U2") (pin "3") (pinfunction "RXD_3") (pintype "passive"))
    )
    (net (code "99") (name "/PA10") (class "Default")
      (node (ref "P2") (pin "33") (pinfunction "33_33") (pintype "passive"))
      (node (ref "U1") (pin "102") (pinfunction "PA10/USART1_RX/TIM1_CH3_102") (pintype "passive"))
      (node (ref "U2") (pin "2") (pinfunction "TXD_2") (pintype "passive"))
    )
    (net (code "100") (name "/PA11") (class "Default")
      (node (ref "CAN_BUS1") (pin "4") (pinfunction "4_4") (pintype "passive"))
      (node (ref "U1") (pin "103") (pinfunction "PA11/USART1_CTS/CAN_RX/TIM1_CH4/USBDM_103") (pintype "passive"))
    )
    (net (code "101") (name "/PA12") (class "Default")
      (node (ref "CAN_BUS1") (pin "3") (pinfunction "3_3") (pintype "passive"))
      (node (ref "U1") (pin "104") (pinfunction "PA12/USART1_RTS/CAN_TX/TIM1_ETR/USBDP_104") (pintype "passive"))
    )
    (net (code "102") (name "/PB10") (class "Default")
      (node (ref "P1") (pin "56") (pinfunction "56_56") (pintype "passive"))
      (node (ref "U1") (pin "69") (pinfunction "PB10/I2C2_SCL/USART3_TX_69") (pintype "passive"))
    )
    (net (code "103") (name "/PB11") (class "Default")
      (node (ref "P1") (pin "55") (pinfunction "55_55") (pintype "passive"))
      (node (ref "U1") (pin "70") (pinfunction "PB11/I2C2_SDA/USART3_RX_70") (pintype "passive"))
    )
    (net (code "104") (name "/PB13") (class "Default")
      (node (ref "P2") (pin "60") (pinfunction "60_60") (pintype "passive"))
      (node (ref "U1") (pin "74") (pinfunction "PB13/SPI2_SCK/I2S2_CK/USART3_CTS/TIM1_CH1N_74") (pintype "passive"))
      (node (ref "U3") (pin "6") (pinfunction "CLK_6") (pintype "passive"))
    )
    (net (code "105") (name "/PB14") (class "Default")
      (node (ref "P2") (pin "57") (pinfunction "57_57") (pintype "passive"))
      (node (ref "U1") (pin "75") (pinfunction "PB14/SPI2_MISO/USART3_RTS/TIM1_CH2N_75") (pintype "passive"))
      (node (ref "U3") (pin "2") (pinfunction "SO_2") (pintype "passive"))
    )
    (net (code "106") (name "/PB15") (class "Default")
      (node (ref "P2") (pin "58") (pinfunction "58_58") (pintype "passive"))
      (node (ref "U1") (pin "76") (pinfunction "PB15/SPI2_MOSI/I2S2_SD/TIM1_CH3N_76") (pintype "passive"))
      (node (ref "U3") (pin "5") (pinfunction "SI_5") (pintype "passive"))
    )
    (net (code "107") (name "/PC6") (class "Default")
      (node (ref "P2") (pin "39") (pinfunction "39_39") (pintype "passive"))
      (node (ref "U1") (pin "96") (pinfunction "PC6/I2S2_MCK/TIM8_CH1/SDIO_D6_96") (pintype "passive"))
    )
    (net (code "108") (name "/PC7") (class "Default")
      (node (ref "P2") (pin "40") (pinfunction "40_40") (pintype "passive"))
      (node (ref "U1") (pin "97") (pinfunction "PC7/I2S3_MCK/TIM8_CH2/SDIO_D7_97") (pintype "passive"))
    )
    (net (code "109") (name "/PC8") (class "Default")
      (node (ref "P2") (pin "37") (pinfunction "37_37") (pintype "passive"))
      (node (ref "U1") (pin "98") (pinfunction "PC8/TIM8_CH3/SDIO_D0_98") (pintype "passive"))
    )
    (net (code "110") (name "/PC9") (class "Default")
      (node (ref "P2") (pin "38") (pinfunction "38_38") (pintype "passive"))
      (node (ref "U1") (pin "99") (pinfunction "PC9/TIM8_CH4/SDIO_D1_99") (pintype "passive"))
    )
    (net (code "111") (name "/PC10") (class "Default")
      (node (ref "P2") (pin "34") (pinfunction "34_34") (pintype "passive"))
      (node (ref "U1") (pin "111") (pinfunction "PC10/UART4_TX/SDIO_D2_111") (pintype "passive"))
    )
    (net (code "112") (name "/PC11") (class "Default")
      (node (ref "P2") (pin "31") (pinfunction "31_31") (pintype "passive"))
      (node (ref "U1") (pin "112") (pinfunction "PC11/UART4_RX/SDIO_D3_112") (pintype "passive"))
    )
    (net (code "113") (name "/PC12") (class "Default")
      (node (ref "P2") (pin "32") (pinfunction "32_32") (pintype "passive"))
      (node (ref "U1") (pin "113") (pinfunction "PC12/UART5_TX/SDIO_CK_113") (pintype "passive"))
    )
    (net (code "114") (name "/PC13") (class "Default")
      (node (ref "P1") (pin "5") (pinfunction "5_5") (pintype "passive"))
      (node (ref "U1") (pin "7") (pinfunction "PC13-TAMPER-RTC_7") (pintype "passive"))
    )
    (net (code "115") (name "/PD2") (class "Default")
      (node (ref "P2") (pin "27") (pinfunction "27_27") (pintype "passive"))
      (node (ref "U1") (pin "116") (pinfunction "PD2/TIM3_ETR/UART5_RX/SDIO_CMD_116") (pintype "passive"))
    )
    (net (code "116") (name "/PG8") (class "Default")
      (node (ref "P2") (pin "41") (pinfunction "41_41") (pintype "passive"))
      (node (ref "U1") (pin "93") (pinfunction "PG8_93") (pintype "passive"))
    )
    (net (code "117") (name "/PG11") (class "Default")
      (node (ref "P2") (pin "17") (pinfunction "17_17") (pintype "passive"))
      (node (ref "U1") (pin "126") (pinfunction "PG11/FSMC_NCE4_2_126") (pintype "passive"))
    )
    (net (code "118") (name "/PG15") (class "Default")
      (node (ref "P2") (pin "11") (pinfunction "11_11") (pintype "passive"))
      (node (ref "U1") (pin "132") (pinfunction "PG15_132") (pintype "passive"))
    )
    (net (code "119") (name "/RESET") (class "Default")
      (node (ref "JTAG1") (pin "15") (pinfunction "RESET#_15") (pintype "passive"))
      (node (ref "P1") (pin "19") (pinfunction "19_19") (pintype "passive"))
      (node (ref "Q2") (pin "3") (pinfunction "C_3") (pintype "passive"))
      (node (ref "R18") (pin "1") (pinfunction "1_1") (pintype "passive"))
      (node (ref "R19") (pin "1") (pinfunction "1_1") (pintype "passive"))
      (node (ref "U1") (pin "25") (pinfunction "NRST_25") (pintype "passive"))
    )
    (net (code "120") (name "/RSTIN") (class "Default")
      (node (ref "C27") (pin "1") (pinfunction "1_1") (pintype "passive"))
      (node (ref "D5") (pin "1") (pinfunction "A_1") (pintype "passive"))
      (node (ref "R12") (pin "2") (pinfunction "2_2") (pintype "passive"))
      (node (ref "RESET_B") (pin "2") (pinfunction "2_2") (pintype "passive"))
      (node (ref "U4") (pin "3") (pinfunction "3_3") (pintype "passive"))
    )
    (net (code "121") (name "/RTS") (class "Default")
      (node (ref "Q2") (pin "1") (pinfunction "E_1") (pintype "passive"))
      (node (ref "R2") (pin "1") (pinfunction "1_1") (pintype "passive"))
      (node (ref "U2") (pin "14") (pinfunction "RTS#_14") (pintype "passive"))
    )
    (net (code "122") (name "/nTRST") (class "Default")
      (node (ref "R19") (pin "2") (pinfunction "2_2") (pintype "passive"))
    )
    (net (code "123") (name "GND") (class "Default")
      (node (ref "BOOT1") (pin "5") (pinfunction "5_5") (pintype "passive"))
      (node (ref "BOOT1") (pin "6") (pinfunction "6_6") (pintype "passive"))
      (node (ref "C1") (pin "2") (pinfunction "2_2") (pintype "passive"))
      (node (ref "C10") (pin "2") (pinfunction "2_2") (pintype "passive"))
      (node (ref "C11") (pin "2") (pinfunction "2_2") (pintype "passive"))
      (node (ref "C12") (pin "1") (pinfunction "1_1") (pintype "passive"))
      (node (ref "C13") (pin "1") (pinfunction "1_1") (pintype "passive"))
      (node (ref "C14") (pin "1") (pinfunction "1_1") (pintype "passive"))
      (node (ref "C15") (pin "1") (pinfunction "1_1") (pintype "passive"))
      (node (ref "C16") (pin "1") (pinfunction "1_1") (pintype "passive"))
      (node (ref "C17") (pin "1") (pinfunction "1_1") (pintype "passive"))
      (node (ref "C18") (pin "1") (pinfunction "1_1") (pintype "passive"))
      (node (ref "C19") (pin "1") (pinfunction "1_1") (pintype "passive"))
      (node (ref "C2") (pin "2") (pinfunction "2_2") (pintype "passive"))
      (node (ref "C20") (pin "1") (pinfunction "1_1") (pintype "passive"))
      (node (ref "C21") (pin "1") (pinfunction "1_1") (pintype "passive"))
      (node (ref "C22") (pin "1") (pinfunction "1_1") (pintype "passive"))
      (node (ref "C23") (pin "1") (pinfunction "1_1") (pintype "passive"))
      (node (ref "C24") (pin "1") (pinfunction "1_1") (pintype "passive"))
      (node (ref "C25") (pin "1") (pinfunction "1_1") (pintype "passive"))
      (node (ref "C26") (pin "1") (pinfunction "1_1") (pintype "passive"))
      (node (ref "C27") (pin "2") (pinfunction "2_2") (pintype "passive"))
      (node (ref "C28") (pin "2") (pinfunction "2_2") (pintype "passive"))
      (node (ref "C29") (pin "2") (pinfunction "2_2") (pintype "passive"))
      (node (ref "C3") (pin "1") (pinfunction "1_1") (pintype "passive"))
      (node (ref "C30") (pin "2") (pinfunction "2_2") (pintype "passive"))
      (node (ref "C31") (pin "2") (pinfunction "2_2") (pintype "passive"))
      (node (ref "C32") (pin "2") (pinfunction "2_2") (pintype "passive"))
      (node (ref "C33") (pin "2") (pinfunction "2_2") (pintype "passive"))
      (node (ref "C34") (pin "2") (pinfunction "2_2") (pintype "passive"))
      (node (ref "C35") (pin "2") (pinfunction "2_2") (pintype "passive"))
      (node (ref "C36") (pin "1") (pinfunction "1_1") (pintype "passive"))
      (node (ref "C37") (pin "2") (pinfunction "2_2") (pintype "passive"))
      (node (ref "C38") (pin "2") (pinfunction "2_2") (pintype "passive"))
      (node (ref "C39") (pin "2") (pinfunction "2_2") (pintype "passive"))
      (node (ref "C4") (pin "2") (pinfunction "2_2") (pintype "passive"))
      (node (ref "C5") (pin "2") (pinfunction "2_2") (pintype "passive"))
      (node (ref "C6") (pin "1") (pinfunction "1_1") (pintype "passive"))
      (node (ref "C7") (pin "1") (pinfunction "1_1") (pintype "passive"))
      (node (ref "C8") (pin "2") (pinfunction "2_2") (pintype "passive"))
      (node (ref "C9") (pin "2") (pinfunction "2_2") (pintype "passive"))
      (node (ref "CT1") (pin "2") (pinfunction "2_2") (pintype "passive"))
      (node (ref "CT2") (pin "2") (pinfunction "2_2") (pintype "passive"))
      (node (ref "JTAG1") (pin "10") (pinfunction "GND_10") (pintype "passive"))
      (node (ref "JTAG1") (pin "12") (pinfunction "GND_12") (pintype "passive"))
      (node (ref "JTAG1") (pin "14") (pinfunction "GND_14") (pintype "passive"))
      (node (ref "JTAG1") (pin "16") (pinfunction "GND_16") (pintype "passive"))
      (node (ref "JTAG1") (pin "18") (pinfunction "GND_18") (pintype "passive"))
      (node (ref "JTAG1") (pin "20") (pinfunction "GND_20") (pintype "passive"))
      (node (ref "JTAG1") (pin "4") (pinfunction "GND_4") (pintype "passive"))
      (node (ref "JTAG1") (pin "6") (pinfunction "GND_6") (pintype "passive"))
      (node (ref "JTAG1") (pin "8") (pinfunction "GND_8") (pintype "passive"))
      (node (ref "P1") (pin "14") (pinfunction "14_14") (pintype "passive"))
      (node (ref "P1") (pin "26") (pinfunction "26_26") (pintype "passive"))
      (node (ref "P1") (pin "57") (pinfunction "57_57") (pintype "passive"))
      (node (ref "P1") (pin "58") (pinfunction "58_58") (pintype "passive"))
      (node (ref "P2") (pin "1") (pinfunction "1_1") (pintype "passive"))
      (node (ref "P2") (pin "14") (pinfunction "14_14") (pintype "passive"))
      (node (ref "P2") (pin "23") (pinfunction "23_23") (pintype "passive"))
      (node (ref "R11") (pin "2") (pinfunction "2_2") (pintype "passive"))
      (node (ref "R16") (pin "1") (pinfunction "1_1") (pintype "passive"))
      (node (ref "R6") (pin "1") (pinfunction "1_1") (pintype "passive"))
      (node (ref "RESET_B") (pin "1") (pinfunction "1_1") (pintype "passive"))
      (node (ref "U1") (pin "107") (pinfunction "VSS_107") (pintype "passive"))
      (node (ref "U1") (pin "120") (pinfunction "VSS_120") (pintype "passive"))
      (node (ref "U1") (pin "130") (pinfunction "VSS_130") (pintype "passive"))
      (node (ref "U1") (pin "143") (pinfunction "VSS_143") (pintype "passive"))
      (node (ref "U1") (pin "16") (pinfunction "VSS_16") (pintype "passive"))
      (node (ref "U1") (pin "30") (pinfunction "VSSA_30") (pintype "passive"))
      (node (ref "U1") (pin "31") (pinfunction "Vref-_31") (pintype "passive"))
      (node (ref "U1") (pin "38") (pinfunction "VSS_38") (pintype "passive"))
      (node (ref "U1") (pin "51") (pinfunction "VSS_51") (pintype "passive"))
      (node (ref "U1") (pin "61") (pinfunction "VSS_61") (pintype "passive"))
      (node (ref "U1") (pin "71") (pinfunction "VSS_71") (pintype "passive"))
      (node (ref "U1") (pin "83") (pinfunction "VSS_83") (pintype "passive"))
      (node (ref "U1") (pin "94") (pinfunction "VSS_94") (pintype "passive"))
      (node (ref "U2") (pin "1") (pinfunction "GND_1") (pintype "passive"))
      (node (ref "U3") (pin "4") (pinfunction "GND_4") (pintype "passive"))
      (node (ref "U4") (pin "1") (pinfunction "1_1") (pintype "passive"))
      (node (ref "U5") (pin "1") (pinfunction "A0_1") (pintype "passive"))
      (node (ref "U5") (pin "2") (pinfunction "A1_2") (pintype "passive"))
      (node (ref "U5") (pin "3") (pinfunction "A2_3") (pintype "passive"))
      (node (ref "U5") (pin "4") (pinfunction "GND_4") (pintype "passive"))
      (node (ref "U5") (pin "7") (pinfunction "WP_7") (pintype "passive"))
      (node (ref "U6") (pin "1") (pinfunction "GND_1") (pintype "passive"))
      (node (ref "USB_232") (pin "5") (pinfunction "GND_5") (pintype "passive"))
      (node (ref "USB_HOST1") (pin "5") (pinfunction "GND_5") (pintype "passive"))
    )
    (net (code "124") (name "Net-(BOOT1-Pad3)") (class "Default")
      (node (ref "BOOT1") (pin "3") (pinfunction "3_3") (pintype "passive"))
      (node (ref "R20") (pin "1") (pinfunction "1_1") (pintype "passive"))
    )
    (net (code "125") (name "Net-(BOOT1-Pad4)") (class "Default")
      (node (ref "BOOT1") (pin "4") (pinfunction "4_4") (pintype "passive"))
      (node (ref "R21") (pin "2") (pinfunction "2_2") (pintype "passive"))
    )
    (net (code "126") (name "Net-(CAN_BUS1-Pad5)") (class "Default")
      (node (ref "CAN_BUS1") (pin "5") (pinfunction "5_5") (pintype "passive"))
      (node (ref "R24") (pin "2") (pinfunction "2_2") (pintype "passive"))
    )
    (net (code "127") (name "Net-(CAN_BUS1-Pad6)") (class "Default")
      (node (ref "CAN_BUS1") (pin "6") (pinfunction "6_6") (pintype "passive"))
      (node (ref "R25") (pin "2") (pinfunction "2_2") (pintype "passive"))
    )
    (net (code "128") (name "Net-(D1-K)") (class "Default")
      (node (ref "D1") (pin "2") (pinfunction "K_2") (pintype "passive"))
      (node (ref "U1") (pin "6") (pinfunction "VBAT_6") (pintype "passive"))
    )
    (net (code "129") (name "Net-(D3-A)") (class "Default")
      (node (ref "D3") (pin "1") (pinfunction "A_1") (pintype "passive"))
      (node (ref "USB_232") (pin "1") (pinfunction "VCC_1") (pintype "passive"))
    )
    (net (code "130") (name "Net-(D4-A)") (class "Default")
      (node (ref "D4") (pin "1") (pinfunction "A_1") (pintype "passive"))
      (node (ref "USB_HOST1") (pin "1") (pinfunction "VCC_1") (pintype "passive"))
    )
    (net (code "131") (name "Net-(LED1-K)") (class "Default")
      (node (ref "LED1") (pin "2") (pinfunction "K_2") (pintype "passive"))
      (node (ref "R5") (pin "2") (pinfunction "2_2") (pintype "passive"))
    )
    (net (code "132") (name "Net-(LED2-K)") (class "Default")
      (node (ref "LED2") (pin "2") (pinfunction "K_2") (pintype "passive"))
      (node (ref "R4") (pin "2") (pinfunction "2_2") (pintype "passive"))
    )
    (net (code "133") (name "Net-(LED3-K)") (class "Default")
      (node (ref "LED3") (pin "2") (pinfunction "K_2") (pintype "passive"))
      (node (ref "R7") (pin "2") (pinfunction "2_2") (pintype "passive"))
    )
    (net (code "134") (name "Net-(POWER1-K)") (class "Default")
      (node (ref "POWER1") (pin "2") (pinfunction "K_2") (pintype "passive"))
      (node (ref "R6") (pin "2") (pinfunction "2_2") (pintype "passive"))
    )
    (net (code "135") (name "Net-(Q1-B)") (class "Default")
      (node (ref "Q1") (pin "2") (pinfunction "B_2") (pintype "passive"))
      (node (ref "R2") (pin "2") (pinfunction "2_2") (pintype "passive"))
    )
    (net (code "136") (name "Net-(Q2-B)") (class "Default")
      (node (ref "Q2") (pin "2") (pinfunction "B_2") (pintype "passive"))
      (node (ref "R3") (pin "2") (pinfunction "2_2") (pintype "passive"))
    )
    (net (code "137") (name "Net-(R18-Pad2)") (class "Default")
      (node (ref "R18") (pin "2") (pinfunction "2_2") (pintype "passive"))
      (node (ref "U4") (pin "2") (pinfunction "2_2") (pintype "passive"))
    )
    (net (code "138") (name "Net-(U2-D+)") (class "Default")
      (node (ref "U2") (pin "5") (pinfunction "D+_5") (pintype "passive"))
      (node (ref "USB_232") (pin "3") (pinfunction "D+_3") (pintype "passive"))
    )
    (net (code "139") (name "Net-(U2-D-)") (class "Default")
      (node (ref "R11") (pin "1") (pinfunction "1_1") (pintype "passive"))
      (node (ref "U2") (pin "6") (pinfunction "D-_6") (pintype "passive"))
      (node (ref "USB_232") (pin "2") (pinfunction "D-_2") (pintype "passive"))
    )
    (net (code "140") (name "Net-(U2-V3)") (class "Default")
      (node (ref "C10") (pin "1") (pinfunction "1_1") (pintype "passive"))
      (node (ref "U2") (pin "4") (pinfunction "V3_4") (pintype "passive"))
    )
    (net (code "141") (name "Net-(U2-XI)") (class "Default")
      (node (ref "C25") (pin "2") (pinfunction "2_2") (pintype "passive"))
      (node (ref "R10") (pin "1") (pinfunction "1_1") (pintype "passive"))
      (node (ref "U2") (pin "7") (pinfunction "XI_7") (pintype "passive"))
      (node (ref "Y3") (pin "2") (pinfunction "OSC2_2") (pintype "passive"))
    )
    (net (code "142") (name "Net-(U2-XO)") (class "Default")
      (node (ref "C24") (pin "2") (pinfunction "2_2") (pintype "passive"))
      (node (ref "R10") (pin "2") (pinfunction "2_2") (pintype "passive"))
      (node (ref "U2") (pin "8") (pinfunction "XO_8") (pintype "passive"))
      (node (ref "Y3") (pin "1") (pinfunction "OSC1_1") (pintype "passive"))
    )
    (net (code "143") (name "Net-(USB_HOST1-D+)") (class "Default")
      (node (ref "R24") (pin "1") (pinfunction "1_1") (pintype "passive"))
      (node (ref "R26") (pin "1") (pinfunction "1_1") (pintype "passive"))
      (node (ref "USB_HOST1") (pin "3") (pinfunction "D+_3") (pintype "passive"))
    )
    (net (code "144") (name "Net-(USB_HOST1-D-)") (class "Default")
      (node (ref "R25") (pin "1") (pinfunction "1_1") (pintype "passive"))
      (node (ref "USB_HOST1") (pin "2") (pinfunction "D-_2") (pintype "passive"))
    )
    (net (code "145") (name "USB_5V1") (class "Default")
      (node (ref "D3") (pin "2") (pinfunction "K_2") (pintype "passive"))
      (node (ref "D4") (pin "2") (pinfunction "K_2") (pintype "passive"))
      (node (ref "F1") (pin "2") (pinfunction "2_2") (pintype "passive"))
      (node (ref "P5") (pin "1") (pinfunction "1_1") (pintype "passive"))
    )
    (net (code "146") (name "VCC5V") (class "Default")
      (node (ref "C36") (pin "2") (pinfunction "2_2") (pintype "passive"))
      (node (ref "F1") (pin "1") (pinfunction "1_1") (pintype "passive"))
      (node (ref "P1") (pin "59") (pinfunction "59_59") (pintype "passive"))
      (node (ref "P1") (pin "60") (pinfunction "60_60") (pintype "passive"))
      (node (ref "P5") (pin "2") (pinfunction "2_2") (pintype "passive"))
      (node (ref "U6") (pin "3") (pinfunction "IN_3") (pintype "passive"))
    )
    (net (code "147") (name "VDD33V") (class "Default")
      (node (ref "BOOT1") (pin "1") (pinfunction "1_1") (pintype "passive"))
      (node (ref "BOOT1") (pin "2") (pinfunction "2_2") (pintype "passive"))
      (node (ref "C11") (pin "1") (pinfunction "1_1") (pintype "passive"))
      (node (ref "C12") (pin "2") (pinfunction "2_2") (pintype "passive"))
      (node (ref "C13") (pin "2") (pinfunction "2_2") (pintype "passive"))
      (node (ref "C14") (pin "2") (pinfunction "2_2") (pintype "passive"))
      (node (ref "C15") (pin "2") (pinfunction "2_2") (pintype "passive"))
      (node (ref "C16") (pin "2") (pinfunction "2_2") (pintype "passive"))
      (node (ref "C17") (pin "2") (pinfunction "2_2") (pintype "passive"))
      (node (ref "C18") (pin "2") (pinfunction "2_2") (pintype "passive"))
      (node (ref "C19") (pin "2") (pinfunction "2_2") (pintype "passive"))
      (node (ref "C20") (pin "2") (pinfunction "2_2") (pintype "passive"))
      (node (ref "C21") (pin "2") (pinfunction "2_2") (pintype "passive"))
      (node (ref "C22") (pin "2") (pinfunction "2_2") (pintype "passive"))
      (node (ref "C23") (pin "2") (pinfunction "2_2") (pintype "passive"))
      (node (ref "C26") (pin "2") (pinfunction "2_2") (pintype "passive"))
      (node (ref "C28") (pin "1") (pinfunction "1_1") (pintype "passive"))
      (node (ref "C29") (pin "1") (pinfunction "1_1") (pintype "passive"))
      (node (ref "C3") (pin "2") (pinfunction "2_2") (pintype "passive"))
      (node (ref "C30") (pin "1") (pinfunction "1_1") (pintype "passive"))
      (node (ref "C31") (pin "1") (pinfunction "1_1") (pintype "passive"))
      (node (ref "C32") (pin "1") (pinfunction "1_1") (pintype "passive"))
      (node (ref "C33") (pin "1") (pinfunction "1_1") (pintype "passive"))
      (node (ref "C34") (pin "1") (pinfunction "1_1") (pintype "passive"))
      (node (ref "C35") (pin "1") (pinfunction "1_1") (pintype "passive"))
      (node (ref "C37") (pin "1") (pinfunction "1_1") (pintype "passive"))
      (node (ref "C38") (pin "1") (pinfunction "1_1") (pintype "passive"))
      (node (ref "C39") (pin "1") (pinfunction "1_1") (pintype "passive"))
      (node (ref "C6") (pin "2") (pinfunction "2_2") (pintype "passive"))
      (node (ref "C7") (pin "2") (pinfunction "2_2") (pintype "passive"))
      (node (ref "C8") (pin "1") (pinfunction "1_1") (pintype "passive"))
      (node (ref "C9") (pin "1") (pinfunction "1_1") (pintype "passive"))
      (node (ref "CT1") (pin "1") (pinfunction "1_1") (pintype "passive"))
      (node (ref "CT2") (pin "1") (pinfunction "1_1") (pintype "passive"))
      (node (ref "D1") (pin "1") (pinfunction "A_1") (pintype "passive"))
      (node (ref "D5") (pin "2") (pinfunction "K_2") (pintype "passive"))
      (node (ref "JTAG1") (pin "1") (pinfunction "VDD_1") (pintype "passive"))
      (node (ref "JTAG1") (pin "2") (pinfunction "VDD_2") (pintype "passive"))
      (node (ref "LED1") (pin "1") (pinfunction "A_1") (pintype "passive"))
      (node (ref "LED2") (pin "1") (pinfunction "A_1") (pintype "passive"))
      (node (ref "LED3") (pin "1") (pinfunction "A_1") (pintype "passive"))
      (node (ref "P1") (pin "13") (pinfunction "13_13") (pintype "passive"))
      (node (ref "P1") (pin "25") (pinfunction "25_25") (pintype "passive"))
      (node (ref "P2") (pin "13") (pinfunction "13_13") (pintype "passive"))
      (node (ref "P2") (pin "2") (pinfunction "2_2") (pintype "passive"))
      (node (ref "P2") (pin "24") (pinfunction "24_24") (pintype "passive"))
      (node (ref "POWER1") (pin "1") (pinfunction "A_1") (pintype "passive"))
      (node (ref "R12") (pin "1") (pinfunction "1_1") (pintype "passive"))
      (node (ref "R13") (pin "1") (pinfunction "1_1") (pintype "passive"))
      (node (ref "R14") (pin "1") (pinfunction "1_1") (pintype "passive"))
      (node (ref "R15") (pin "1") (pinfunction "1_1") (pintype "passive"))
      (node (ref "R17") (pin "2") (pinfunction "2_2") (pintype "passive"))
      (node (ref "R22") (pin "2") (pinfunction "2_2") (pintype "passive"))
      (node (ref "R23") (pin "1") (pinfunction "1_1") (pintype "passive"))
      (node (ref "R26") (pin "2") (pinfunction "2_2") (pintype "passive"))
      (node (ref "U1") (pin "108") (pinfunction "VDD_108") (pintype "passive"))
      (node (ref "U1") (pin "121") (pinfunction "VDD_121") (pintype "passive"))
      (node (ref "U1") (pin "131") (pinfunction "VDD_131") (pintype "passive"))
      (node (ref "U1") (pin "144") (pinfunction "VDD_144") (pintype "passive"))
      (node (ref "U1") (pin "17") (pinfunction "VDD_17") (pintype "passive"))
      (node (ref "U1") (pin "32") (pinfunction "Vref+_32") (pintype "passive"))
      (node (ref "U1") (pin "33") (pinfunction "VDDA_33") (pintype "passive"))
      (node (ref "U1") (pin "39") (pinfunction "VDD_39") (pintype "passive"))
      (node (ref "U1") (pin "52") (pinfunction "VDD_52") (pintype "passive"))
      (node (ref "U1") (pin "62") (pinfunction "VDD_62") (pintype "passive"))
      (node (ref "U1") (pin "72") (pinfunction "VDD_72") (pintype "passive"))
      (node (ref "U1") (pin "84") (pinfunction "VDD_84") (pintype "passive"))
      (node (ref "U1") (pin "95") (pinfunction "VDD_95") (pintype "passive"))
      (node (ref "U2") (pin "16") (pinfunction "VCC_16") (pintype "passive"))
      (node (ref "U3") (pin "3") (pinfunction "WP#_3") (pintype "passive"))
      (node (ref "U3") (pin "7") (pinfunction "HOLD_7") (pintype "passive"))
      (node (ref "U3") (pin "8") (pinfunction "VCC_8") (pintype "passive"))
      (node (ref "U4") (pin "4") (pinfunction "4_4") (pintype "passive"))
      (node (ref "U5") (pin "8") (pinfunction "VCC_8") (pintype "passive"))
      (node (ref "U6") (pin "2") (pinfunction "OUT_2") (pintype "passive"))
      (node (ref "U6") (pin "4") (pinfunction "OUT_4") (pintype "passive"))
    )
    (net (code "148") (name "unconnected-(JTAG1-NC-Pad11)") (class "Default")
      (node (ref "JTAG1") (pin "11") (pinfunction "NC_11") (pintype "passive"))
    )
    (net (code "149") (name "unconnected-(JTAG1-NC-Pad17)") (class "Default")
      (node (ref "JTAG1") (pin "17") (pinfunction "NC_17") (pintype "passive"))
    )
    (net (code "150") (name "unconnected-(JTAG1-NC-Pad19)") (class "Default")
      (node (ref "JTAG1") (pin "19") (pinfunction "NC_19") (pintype "passive"))
    )
    (net (code "151") (name "unconnected-(P2-Pad42)") (class "Default")
      (node (ref "P2") (pin "42") (pinfunction "42_42") (pintype "passive"))
    )
    (net (code "152") (name "unconnected-(U1-NC-Pad106)") (class "Default")
      (node (ref "U1") (pin "106") (pinfunction "NC_106") (pintype "passive"))
    )
    (net (code "153") (name "unconnected-(U2-CTS#-Pad9)") (class "Default")
      (node (ref "U2") (pin "9") (pinfunction "CTS#_9") (pintype "passive"))
    )
    (net (code "154") (name "unconnected-(U2-DCD#-Pad12)") (class "Default")
      (node (ref "U2") (pin "12") (pinfunction "DCD#_12") (pintype "passive"))
    )
    (net (code "155") (name "unconnected-(U2-DSR#-Pad10)") (class "Default")
      (node (ref "U2") (pin "10") (pinfunction "DSR#_10") (pintype "passive"))
    )
    (net (code "156") (name "unconnected-(U2-R232-Pad15)") (class "Default")
      (node (ref "U2") (pin "15") (pinfunction "R232_15") (pintype "passive"))
    )
    (net (code "157") (name "unconnected-(U2-RI#-Pad11)") (class "Default")
      (node (ref "U2") (pin "11") (pinfunction "RI#_11") (pintype "passive"))
    )
    (net (code "158") (name "unconnected-(USB_232-NC-Pad4)") (class "Default")
      (node (ref "USB_232") (pin "4") (pinfunction "NC_4") (pintype "passive"))
    )
    (net (code "159") (name "unconnected-(USB_HOST1-NC-Pad4)") (class "Default")
      (node (ref "USB_HOST1") (pin "4") (pinfunction "NC_4") (pintype "passive"))
    )
  )
)
